# design.net
KiCad netlist of a schematic drawn in Altium Designer
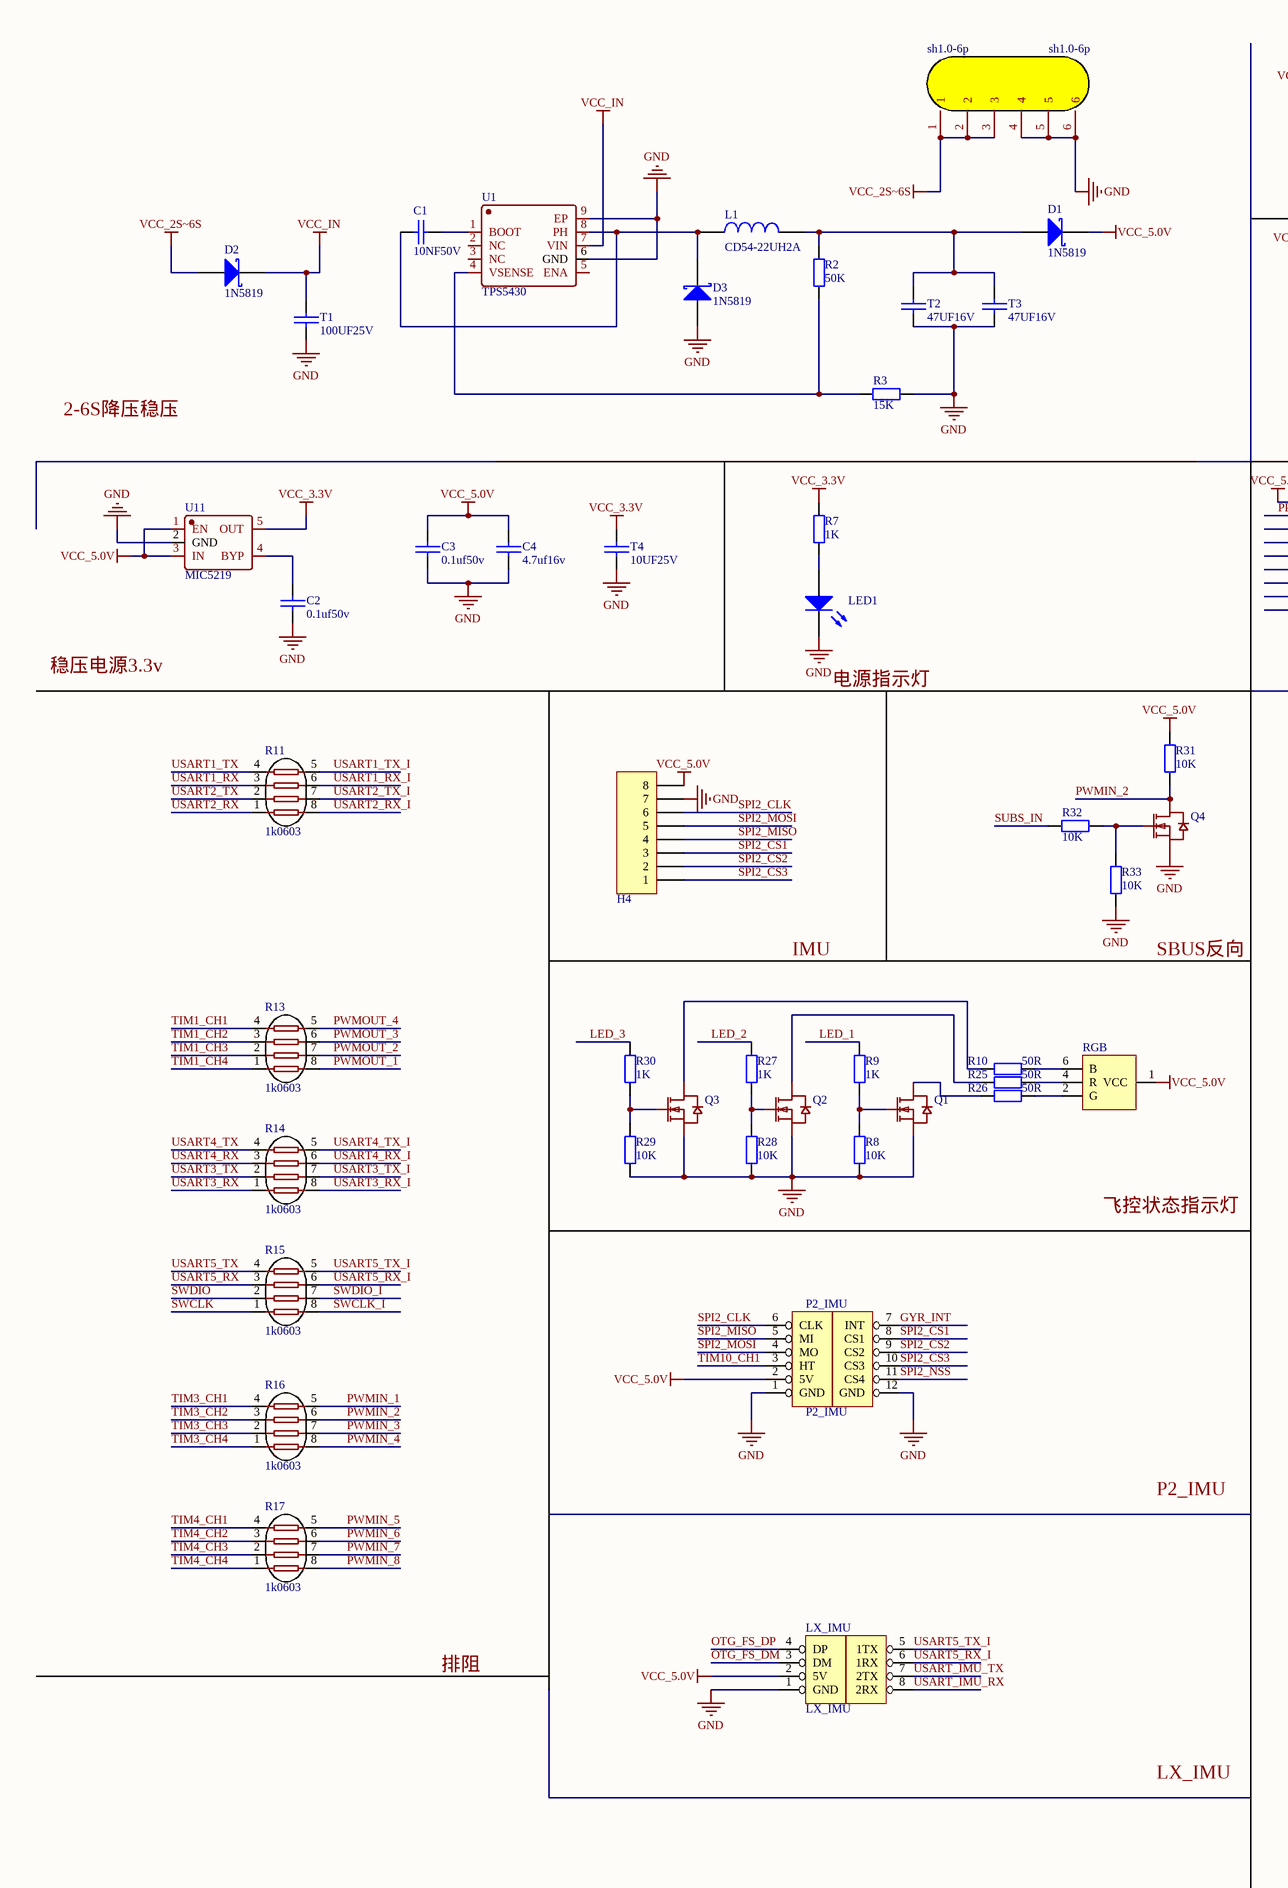
[diagram p0: 飞控板.SchDoc, left]
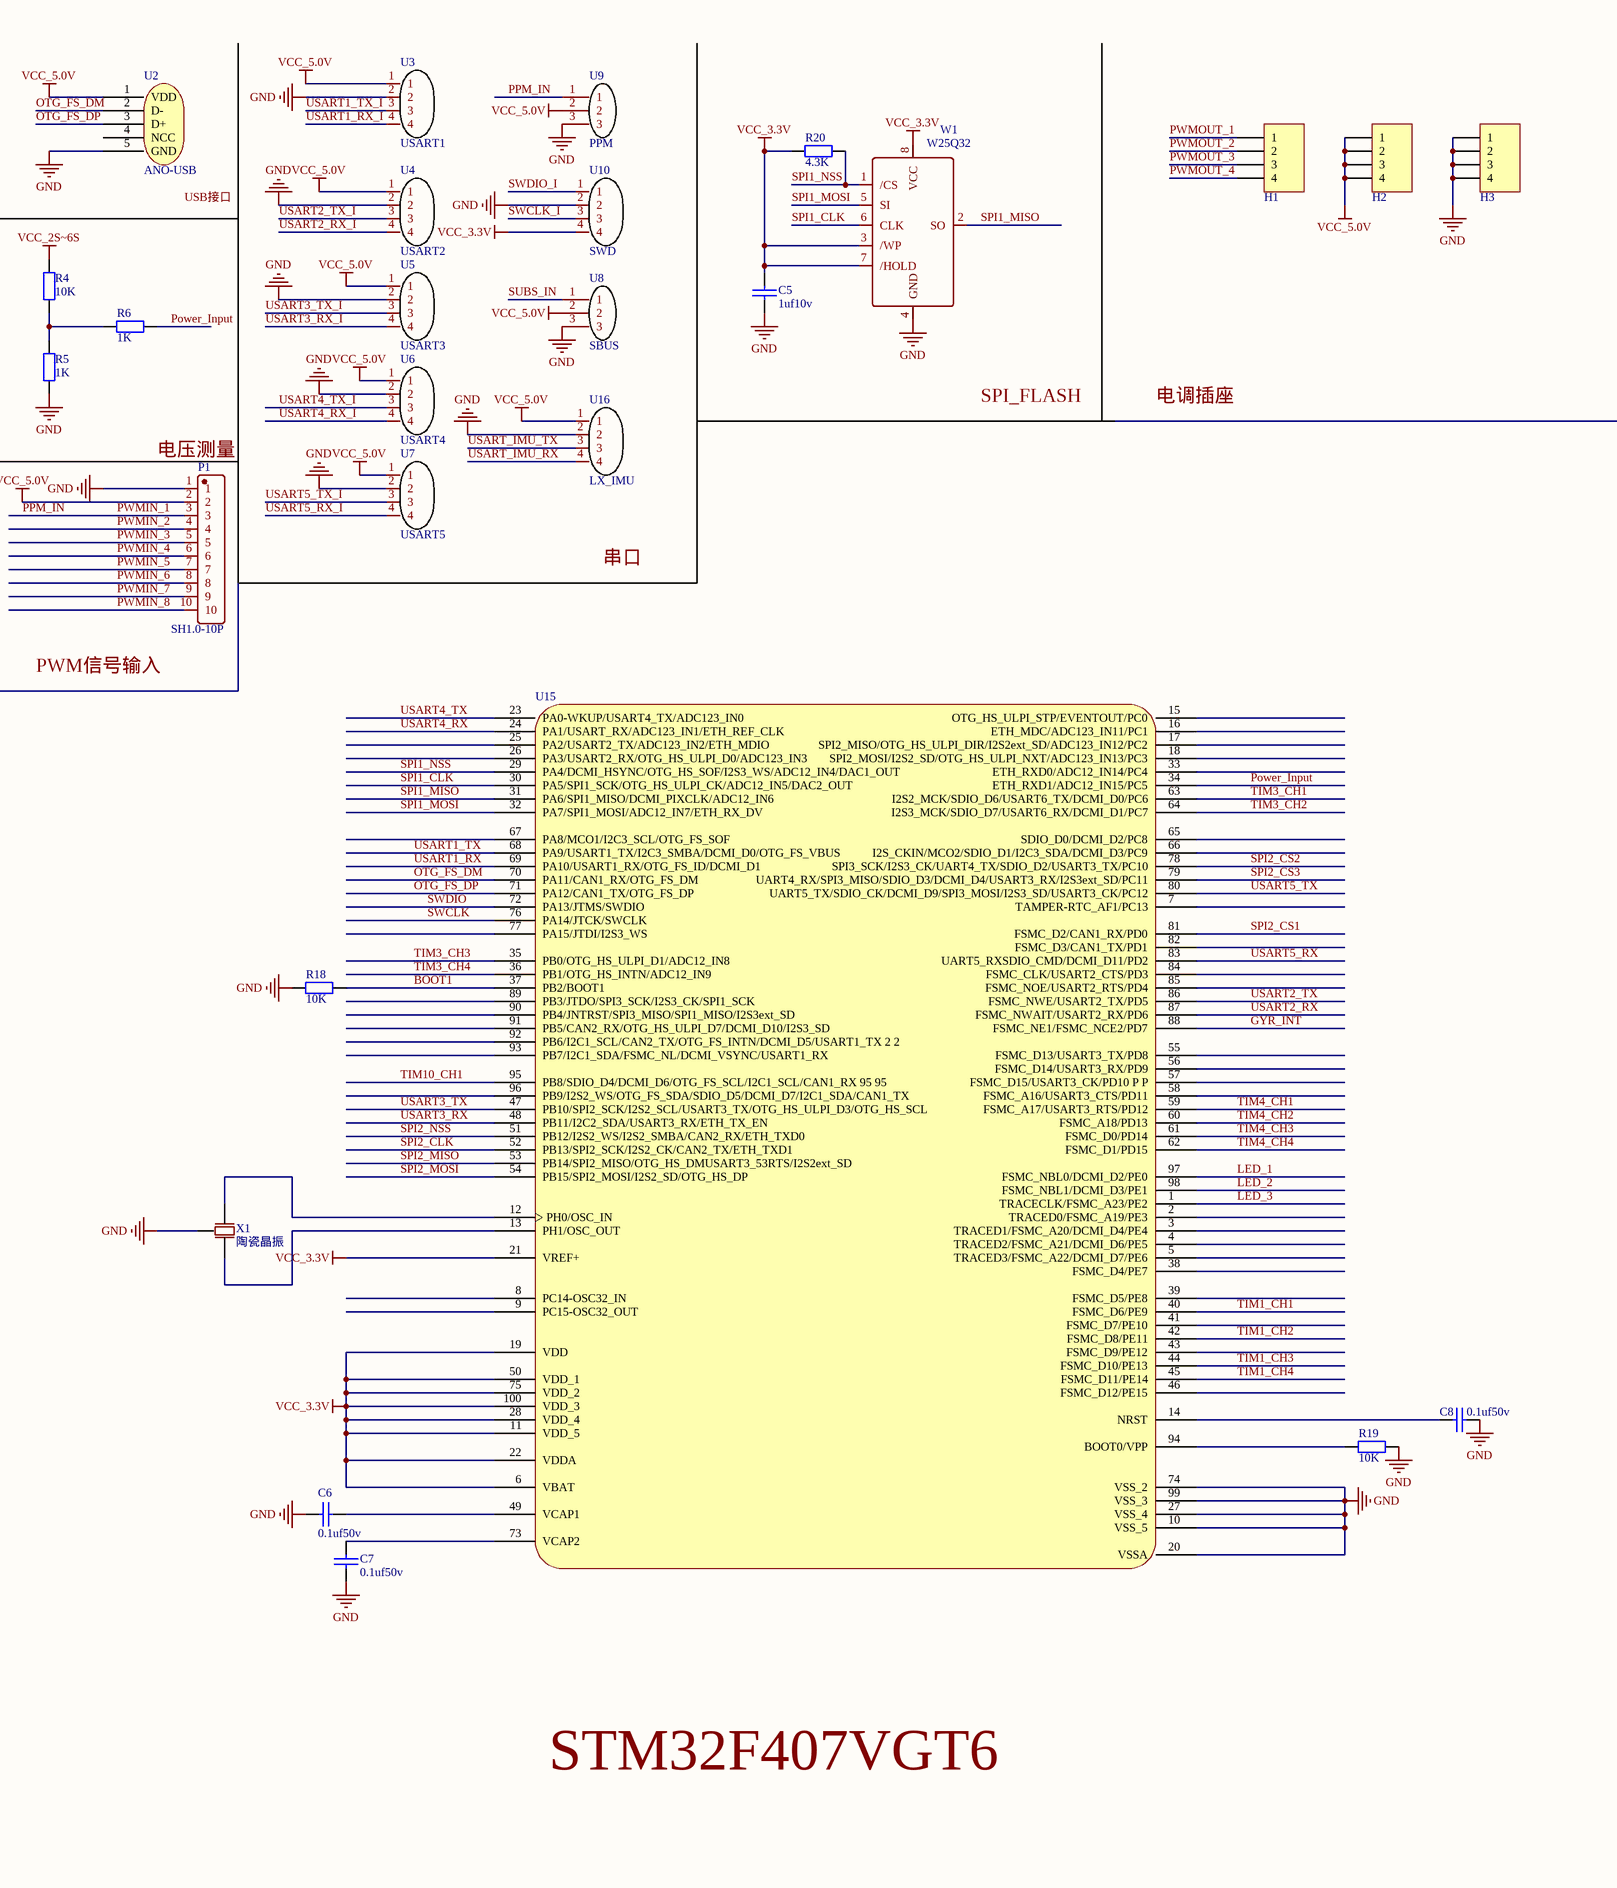
[diagram p1: 飞控板.SchDoc, right]

(export (version "E")
  (design (tool "Eeschema 10.0.6"))
  (components
    (comp (ref "C1")
      (value "10NF50V")
      (footprint "0805C")
      (description "无极性电容")
      (libsource (lib "电容") (part "CAP"))
    )
    (comp (ref "C2")
      (value "0.1uf50v")
      (footprint "0805C")
      (description "无极性电容")
      (libsource (lib "电容") (part "CAP"))
    )
    (comp (ref "C3")
      (value "0.1uf50v")
      (footprint "0805C")
      (description "无极性电容")
      (libsource (lib "电容") (part "CAP"))
    )
    (comp (ref "C4")
      (value "4.7uf16v")
      (footprint "0805C")
      (description "无极性电容")
      (libsource (lib "电容") (part "CAP"))
    )
    (comp (ref "C5")
      (value "1uf10v")
      (footprint "0805C")
      (description "无极性电容")
      (libsource (lib "电容") (part "CAP"))
    )
    (comp (ref "C6")
      (value "0.1uf50v")
      (footprint "0805C")
      (description "无极性电容")
      (libsource (lib "电容") (part "CAP"))
    )
    (comp (ref "C7")
      (value "0.1uf50v")
      (footprint "0805C")
      (description "无极性电容")
      (libsource (lib "电容") (part "CAP"))
    )
    (comp (ref "C8")
      (value "0.1uf50v")
      (footprint "0805C")
      (description "无极性电容")
      (libsource (lib "电容") (part "CAP"))
    )
    (comp (ref "D1")
      (value "1N5819")
      (footprint "DO214AC_SMA")
      (description "贴片肖特基二极管")
      (libsource (lib "1.二极管") (part "1N5817-5819SMD"))
    )
    (comp (ref "D2")
      (value "1N5819")
      (footprint "DO214AC_SMA")
      (description "贴片肖特基二极管")
      (libsource (lib "1.二极管") (part "1N5817-5819SMD"))
    )
    (comp (ref "D3")
      (value "1N5819")
      (footprint "DO214AC_SMA")
      (description "贴片肖特基二极管")
      (libsource (lib "1.二极管") (part "1N5817-5819SMD"))
    )
    (comp (ref "H1")
      (value "Header 4")
      (footprint "HDR1X4")
      (description "Header, 4-Pin")
      (fields (field (name "PUBLISHER") "Altium Limited"))
      (libsource (lib "9.接插件 连接器") (part "Header 4"))
    )
    (comp (ref "H2")
      (value "Header 4")
      (footprint "HDR1X4")
      (description "Header, 4-Pin")
      (fields (field (name "PUBLISHER") "Altium Limited"))
      (libsource (lib "9.接插件 连接器") (part "Header 4"))
    )
    (comp (ref "H3")
      (value "Header 4")
      (footprint "HDR1X4")
      (description "Header, 4-Pin")
      (fields (field (name "PUBLISHER") "Altium Limited"))
      (libsource (lib "9.接插件 连接器") (part "Header 4"))
    )
    (comp (ref "H4")
      (value "Header 8")
      (footprint "HDR1X8")
      (description "Header, 8-Pin")
      (fields (field (name "PUBLISHER") "Altium Limited"))
      (libsource (lib "9.接插件 连接器") (part "Header 8"))
    )
    (comp (ref "L1")
      (value "CD54-22UH2A")
      (footprint "CDRH73")
      (description "INDUCTOR")
      (libsource (lib "电感") (part "INDUCTOR"))
    )
    (comp (ref "LED1") (value "~") (footprint "LED-1206") (libsource (lib "1.二极管") (part "LED1206")))
    (comp (ref "LX_IMU") (value "LX_IMU") (footprint "LX_IMU") (libsource (lib "LX_IMU") (part "LX_IMU")))
    (comp (ref "P1")
      (value "SH1.0-10P")
      (footprint "SH1.0-10P")
      (libsource (lib "SH1.0-10P") (part "SH1.0-10P"))
    )
    (comp (ref "P2_IMU")
      (value "P2_IMU")
      (footprint "P2_IMU")
      (libsource (lib "P2_IMU") (part "Component_1"))
    )
    (comp (ref "Q1") (value "~") (footprint "SI2310") (libsource (lib "SI2310") (part "SI2310")))
    (comp (ref "Q2") (value "~") (footprint "SI2310") (libsource (lib "SI2310") (part "SI2310")))
    (comp (ref "Q3") (value "~") (footprint "SI2310") (libsource (lib "SI2310") (part "SI2310")))
    (comp (ref "Q4") (value "~") (footprint "SI2310") (libsource (lib "SI2310") (part "SI2310")))
    (comp (ref "R2")
      (value "50K")
      (footprint "0805R")
      (description "0805贴片电阻")
      (libsource (lib "") (part "Res_0805_2"))
    )
    (comp (ref "R3")
      (value "15K")
      (footprint "0805R")
      (description "0805贴片电阻")
      (libsource (lib "0.电阻电容电感") (part "Res_0805"))
    )
    (comp (ref "R4")
      (value "10K")
      (footprint "0805R")
      (description "0805贴片电阻")
      (libsource (lib "") (part "Res_0805_2"))
    )
    (comp (ref "R5")
      (value "1K")
      (footprint "0805R")
      (description "0805贴片电阻")
      (libsource (lib "") (part "Res_0805_2"))
    )
    (comp (ref "R6")
      (value "1K")
      (footprint "0805R")
      (description "0805贴片电阻")
      (libsource (lib "0.电阻电容电感") (part "Res_0805"))
    )
    (comp (ref "R7")
      (value "1K")
      (footprint "0805R")
      (description "0805贴片电阻")
      (libsource (lib "") (part "Res_0805_2"))
    )
    (comp (ref "R8")
      (value "10K")
      (footprint "0805R")
      (description "0805贴片电阻")
      (libsource (lib "") (part "Res_0805_2"))
    )
    (comp (ref "R9")
      (value "1K")
      (footprint "0805R")
      (description "0805贴片电阻")
      (libsource (lib "") (part "Res_0805_2"))
    )
    (comp (ref "R10")
      (value "50R")
      (footprint "0805R")
      (description "0805贴片电阻")
      (libsource (lib "") (part "Res_0805_1"))
    )
    (comp (ref "R11") (value "1k0603") (footprint "1k0603") (libsource (lib "1k0603") (part "1k0603")))
    (comp (ref "R13") (value "1k0603") (footprint "1k0603") (libsource (lib "1k0603") (part "1k0603")))
    (comp (ref "R14") (value "1k0603") (footprint "1k0603") (libsource (lib "1k0603") (part "1k0603")))
    (comp (ref "R15") (value "1k0603") (footprint "1k0603") (libsource (lib "1k0603") (part "1k0603")))
    (comp (ref "R16") (value "1k0603") (footprint "1k0603") (libsource (lib "1k0603") (part "1k0603")))
    (comp (ref "R17") (value "1k0603") (footprint "1k0603") (libsource (lib "1k0603") (part "1k0603")))
    (comp (ref "R18")
      (value "10K")
      (footprint "0805R")
      (description "0805贴片电阻")
      (libsource (lib "") (part "Res_0805_1"))
    )
    (comp (ref "R19")
      (value "10K")
      (footprint "0805R")
      (description "0805贴片电阻")
      (libsource (lib "") (part "Res_0805_1"))
    )
    (comp (ref "R20")
      (value "4.3K")
      (footprint "0805R")
      (description "0805贴片电阻")
      (libsource (lib "") (part "Res_0805_1"))
    )
    (comp (ref "R25")
      (value "50R")
      (footprint "0805R")
      (description "0805贴片电阻")
      (libsource (lib "") (part "Res_0805_1"))
    )
    (comp (ref "R26")
      (value "50R")
      (footprint "0805R")
      (description "0805贴片电阻")
      (libsource (lib "") (part "Res_0805_1"))
    )
    (comp (ref "R27")
      (value "1K")
      (footprint "0805R")
      (description "0805贴片电阻")
      (libsource (lib "") (part "Res_0805_2"))
    )
    (comp (ref "R28")
      (value "10K")
      (footprint "0805R")
      (description "0805贴片电阻")
      (libsource (lib "") (part "Res_0805_2"))
    )
    (comp (ref "R29")
      (value "10K")
      (footprint "0805R")
      (description "0805贴片电阻")
      (libsource (lib "") (part "Res_0805_2"))
    )
    (comp (ref "R30")
      (value "1K")
      (footprint "0805R")
      (description "0805贴片电阻")
      (libsource (lib "") (part "Res_0805_2"))
    )
    (comp (ref "R31")
      (value "10K")
      (footprint "0805R")
      (description "0805贴片电阻")
      (libsource (lib "") (part "Res_0805_2"))
    )
    (comp (ref "R32")
      (value "10K")
      (footprint "0805R")
      (description "0805贴片电阻")
      (libsource (lib "0.电阻电容电感") (part "Res_0805"))
    )
    (comp (ref "R33")
      (value "10K")
      (footprint "0805R")
      (description "0805贴片电阻")
      (libsource (lib "") (part "Res_0805_3"))
    )
    (comp (ref "RGB")
      (value "~")
      (footprint "RGB_LED")
      (description "RGB")
      (libsource (lib "RGB灯") (part "RGB"))
    )
    (comp (ref "sh1.0-6p")
      (value "sh1.0-6p")
      (footprint "sh1.0-6p")
      (libsource (lib "sh1.0-6p") (part "sh1.0-6p"))
    )
    (comp (ref "T1")
      (value "100UF25V")
      (footprint "0805C")
      (description "无极性电容")
      (libsource (lib "电容") (part "CAP"))
    )
    (comp (ref "T2")
      (value "47UF16V")
      (footprint "0805C")
      (description "无极性电容")
      (libsource (lib "电容") (part "CAP"))
    )
    (comp (ref "T3")
      (value "47UF16V")
      (footprint "0805C")
      (description "无极性电容")
      (libsource (lib "电容") (part "CAP"))
    )
    (comp (ref "T4")
      (value "10UF25V")
      (footprint "0805C")
      (description "无极性电容")
      (libsource (lib "电容") (part "CAP"))
    )
    (comp (ref "U1") (value "TPS5430") (footprint "TPS5430") (libsource (lib "TPS5430") (part "TPS5430")))
    (comp (ref "U2") (value "ANO-USB") (footprint "ANO-USB") (libsource (lib "ANO-USB") (part "ANO-USB")))
    (comp (ref "U3") (value "USART1") (footprint "SH1.0-4P") (libsource (lib "SH1.0-4P") (part "SH1.0-4P")))
    (comp (ref "U4") (value "USART2") (footprint "SH1.0-4P") (libsource (lib "SH1.0-4P") (part "SH1.0-4P")))
    (comp (ref "U5") (value "USART3") (footprint "SH1.0-4P") (libsource (lib "SH1.0-4P") (part "SH1.0-4P")))
    (comp (ref "U6") (value "USART4") (footprint "SH1.0-4P") (libsource (lib "SH1.0-4P") (part "SH1.0-4P")))
    (comp (ref "U7") (value "USART5") (footprint "SH1.0-4P") (libsource (lib "SH1.0-4P") (part "SH1.0-4P")))
    (comp (ref "U8") (value "SBUS") (footprint "SH1.0-3P") (libsource (lib "SH1.0-3P") (part "SH1.0-3P")))
    (comp (ref "U9") (value "PPM") (footprint "SH1.0-3P") (libsource (lib "SH1.0-3P") (part "SH1.0-3P")))
    (comp (ref "U10") (value "SWD") (footprint "SH1.0-4P") (libsource (lib "SH1.0-4P") (part "SH1.0-4P")))
    (comp (ref "U11") (value "MIC5219") (footprint "MIC5219") (libsource (lib "MIC5219") (part "MIC5219")))
    (comp (ref "U15")
      (value "~")
      (footprint "STM32F407VGT6=")
      (libsource (lib "STM32F407VGT6=") (part "STM32F407VGT6="))
    )
    (comp (ref "U16") (value "LX_IMU") (footprint "SH1.0-4P") (libsource (lib "SH1.0-4P") (part "SH1.0-4P")))
    (comp (ref "W1") (value "W25Q32") (footprint "W25Q32") (libsource (lib "W25Q32") (part "W25Q32")))
    (comp (ref "X1") (value "陶瓷晶振") (footprint "陶瓷晶振") (libsource (lib "陶瓷晶振") (part "陶瓷晶振")))
  )
  (nets
    (net (code "2") (name "/BOOT1") (class "Default")
      (node (ref "R18") (pin "1") (pinfunction "1_1") (pintype "passive"))
      (node (ref "U15") (pin "37") (pinfunction "PB2/BOOT1_37") (pintype "passive"))
    )
    (net (code "3") (name "/GYR_INT") (class "Default")
      (node (ref "P2_IMU") (pin "7") (pinfunction "INT_7") (pintype "passive"))
      (node (ref "U15") (pin "88") (pinfunction "FSMC_NE1/FSMC_NCE2/PD7_88") (pintype "passive"))
    )
    (net (code "5") (name "/LED_1") (class "Default")
      (node (ref "R9") (pin "1") (pinfunction "1_1") (pintype "passive"))
      (node (ref "U15") (pin "97") (pinfunction "FSMC_NBL0/DCMI_D2/PE0_97") (pintype "passive"))
    )
    (net (code "6") (name "/LED_2") (class "Default")
      (node (ref "R27") (pin "1") (pinfunction "1_1") (pintype "passive"))
      (node (ref "U15") (pin "98") (pinfunction "FSMC_NBL1/DCMI_D3/PE1_98") (pintype "passive"))
    )
    (net (code "7") (name "/LED_3") (class "Default")
      (node (ref "R30") (pin "1") (pinfunction "1_1") (pintype "passive"))
      (node (ref "U15") (pin "1") (pinfunction "TRACECLK/FSMC_A23/PE2_1") (pintype "passive"))
    )
    (net (code "9") (name "/OTG_FS_DM") (class "Default")
      (node (ref "LX_IMU") (pin "3") (pinfunction "DM_3") (pintype "passive"))
      (node (ref "U15") (pin "70") (pinfunction "PA11/CAN1_RX/OTG_FS_DM_70") (pintype "passive"))
      (node (ref "U2") (pin "2") (pinfunction "D-_2") (pintype "passive"))
    )
    (net (code "10") (name "/OTG_FS_DP") (class "Default")
      (node (ref "LX_IMU") (pin "4") (pinfunction "DP_4") (pintype "passive"))
      (node (ref "U15") (pin "71") (pinfunction "PA12/CAN1_TX/OTG_FS_DP_71") (pintype "passive"))
      (node (ref "U2") (pin "3") (pinfunction "D+_3") (pintype "passive"))
    )
    (net (code "12") (name "/PPM_IN") (class "Default")
      (node (ref "P1") (pin "3") (pinfunction "3_3") (pintype "passive"))
      (node (ref "R16") (pin "5") (pinfunction "5_5") (pintype "passive"))
      (node (ref "U9") (pin "1") (pinfunction "1_1") (pintype "passive"))
    )
    (net (code "13") (name "/PWMIN_2") (class "Default")
      (node (ref "P1") (pin "4") (pinfunction "4_4") (pintype "passive"))
      (node (ref "Q4") (pin "3") (pinfunction "D_3") (pintype "passive"))
      (node (ref "R16") (pin "6") (pinfunction "6_6") (pintype "passive"))
      (node (ref "R31") (pin "2") (pinfunction "2_2") (pintype "passive"))
    )
    (net (code "14") (name "/PWMIN_3") (class "Default")
      (node (ref "P1") (pin "5") (pinfunction "5_5") (pintype "passive"))
      (node (ref "R16") (pin "7") (pinfunction "7_7") (pintype "passive"))
    )
    (net (code "15") (name "/PWMIN_4") (class "Default")
      (node (ref "P1") (pin "6") (pinfunction "6_6") (pintype "passive"))
      (node (ref "R16") (pin "8") (pinfunction "8_8") (pintype "passive"))
    )
    (net (code "16") (name "/PWMIN_5") (class "Default")
      (node (ref "P1") (pin "7") (pinfunction "7_7") (pintype "passive"))
      (node (ref "R17") (pin "5") (pinfunction "5_5") (pintype "passive"))
    )
    (net (code "17") (name "/PWMIN_6") (class "Default")
      (node (ref "P1") (pin "8") (pinfunction "8_8") (pintype "passive"))
      (node (ref "R17") (pin "6") (pinfunction "6_6") (pintype "passive"))
    )
    (net (code "18") (name "/PWMIN_7") (class "Default")
      (node (ref "P1") (pin "9") (pinfunction "9_9") (pintype "passive"))
      (node (ref "R17") (pin "7") (pinfunction "7_7") (pintype "passive"))
    )
    (net (code "19") (name "/PWMIN_8") (class "Default")
      (node (ref "P1") (pin "10") (pinfunction "10_10") (pintype "passive"))
      (node (ref "R17") (pin "8") (pinfunction "8_8") (pintype "passive"))
    )
    (net (code "20") (name "/PWMOUT_1") (class "Default")
      (node (ref "H1") (pin "1") (pinfunction "1_1") (pintype "passive"))
      (node (ref "R13") (pin "8") (pinfunction "8_8") (pintype "passive"))
    )
    (net (code "21") (name "/PWMOUT_2") (class "Default")
      (node (ref "H1") (pin "2") (pinfunction "2_2") (pintype "passive"))
      (node (ref "R13") (pin "7") (pinfunction "7_7") (pintype "passive"))
    )
    (net (code "22") (name "/PWMOUT_3") (class "Default")
      (node (ref "H1") (pin "3") (pinfunction "3_3") (pintype "passive"))
      (node (ref "R13") (pin "6") (pinfunction "6_6") (pintype "passive"))
    )
    (net (code "23") (name "/PWMOUT_4") (class "Default")
      (node (ref "H1") (pin "4") (pinfunction "4_4") (pintype "passive"))
      (node (ref "R13") (pin "5") (pinfunction "5_5") (pintype "passive"))
    )
    (net (code "25") (name "/Power_Input") (class "Default")
      (node (ref "R6") (pin "2") (pinfunction "2_2") (pintype "passive"))
      (node (ref "U15") (pin "34") (pinfunction "ETH_RXD1/ADC12_IN15/PC5_34") (pintype "passive"))
    )
    (net (code "27") (name "/SPI1_CLK") (class "Default")
      (node (ref "U15") (pin "30") (pinfunction "PA5/SPI1_SCK/OTG_HS_ULPI_CK/ADC12_IN5/DAC2_OUT_30") (pintype "passive"))
      (node (ref "W1") (pin "6") (pinfunction "CLK_6") (pintype "passive"))
    )
    (net (code "28") (name "/SPI1_MISO") (class "Default")
      (node (ref "U15") (pin "31") (pinfunction "PA6/SPI1_MISO/DCMI_PIXCLK/ADC12_IN6_31") (pintype "passive"))
      (node (ref "W1") (pin "2") (pinfunction "SO_2") (pintype "passive"))
    )
    (net (code "29") (name "/SPI1_MOSI") (class "Default")
      (node (ref "U15") (pin "32") (pinfunction "PA7/SPI1_MOSI/ADC12_IN7/ETH_RX_DV_32") (pintype "passive"))
      (node (ref "W1") (pin "5") (pinfunction "SI_5") (pintype "passive"))
    )
    (net (code "30") (name "/SPI1_NSS") (class "Default")
      (node (ref "R20") (pin "1") (pinfunction "1_1") (pintype "passive"))
      (node (ref "U15") (pin "29") (pinfunction "PA4/DCMI_HSYNC/OTG_HS_SOF/I2S3_WS/ADC12_IN4/DAC1_OUT_29") (pintype "passive"))
      (node (ref "W1") (pin "1") (pinfunction "/CS_1") (pintype "passive"))
    )
    (net (code "31") (name "/SPI2_CLK") (class "Default")
      (node (ref "H4") (pin "6") (pinfunction "6_6") (pintype "passive"))
      (node (ref "P2_IMU") (pin "6") (pinfunction "CLK_6") (pintype "passive"))
      (node (ref "U15") (pin "52") (pinfunction "PB13/SPI2_SCK/I2S2_CK/CAN2_TX/ETH_TXD1_52") (pintype "passive"))
    )
    (net (code "32") (name "/SPI2_CS1") (class "Default")
      (node (ref "H4") (pin "3") (pinfunction "3_3") (pintype "passive"))
      (node (ref "P2_IMU") (pin "8") (pinfunction "CS1_8") (pintype "passive"))
      (node (ref "U15") (pin "81") (pinfunction "FSMC_D2/CAN1_RX/PD0_81") (pintype "passive"))
    )
    (net (code "33") (name "/SPI2_CS2") (class "Default")
      (node (ref "H4") (pin "2") (pinfunction "2_2") (pintype "passive"))
      (node (ref "P2_IMU") (pin "9") (pinfunction "CS2_9") (pintype "passive"))
      (node (ref "U15") (pin "78") (pinfunction "SPI3_SCK/I2S3_CK/UART4_TX/SDIO_D2/USART3_TX/PC10_78") (pintype "passive"))
    )
    (net (code "34") (name "/SPI2_CS3") (class "Default")
      (node (ref "H4") (pin "1") (pinfunction "1_1") (pintype "passive"))
      (node (ref "P2_IMU") (pin "10") (pinfunction "CS3_10") (pintype "passive"))
      (node (ref "U15") (pin "79") (pinfunction "UART4_RX/SPI3_MISO/SDIO_D3/DCMI_D4/USART3_RX/I2S3ext_SD/PC11_79") (pintype "passive"))
    )
    (net (code "35") (name "/SPI2_MISO") (class "Default")
      (node (ref "H4") (pin "4") (pinfunction "4_4") (pintype "passive"))
      (node (ref "P2_IMU") (pin "5") (pinfunction "MI_5") (pintype "passive"))
      (node (ref "U15") (pin "53") (pinfunction "PB14/SPI2_MISO/OTG_HS_DMUSART3_53RTS/I2S2ext_SD_53") (pintype "passive"))
    )
    (net (code "36") (name "/SPI2_MOSI") (class "Default")
      (node (ref "H4") (pin "5") (pinfunction "5_5") (pintype "passive"))
      (node (ref "P2_IMU") (pin "4") (pinfunction "MO_4") (pintype "passive"))
      (node (ref "U15") (pin "54") (pinfunction "PB15/SPI2_MOSI/I2S2_SD/OTG_HS_DP_54") (pintype "passive"))
    )
    (net (code "37") (name "/SPI2_NSS") (class "Default")
      (node (ref "P2_IMU") (pin "11") (pinfunction "CS4_11") (pintype "passive"))
      (node (ref "U15") (pin "51") (pinfunction "PB12/I2S2_WS/I2S2_SMBA/CAN2_RX/ETH_TXD0_51") (pintype "passive"))
    )
    (net (code "40") (name "/SUBS_IN") (class "Default")
      (node (ref "R32") (pin "1") (pinfunction "1_1") (pintype "passive"))
      (node (ref "U8") (pin "1") (pinfunction "1_1") (pintype "passive"))
    )
    (net (code "41") (name "/SWCLK") (class "Default")
      (node (ref "R15") (pin "1") (pinfunction "1_1") (pintype "passive"))
      (node (ref "U15") (pin "76") (pinfunction "PA14/JTCK/SWCLK_76") (pintype "passive"))
    )
    (net (code "42") (name "/SWCLK_I") (class "Default")
      (node (ref "R15") (pin "8") (pinfunction "8_8") (pintype "passive"))
      (node (ref "U10") (pin "3") (pinfunction "3_3") (pintype "passive"))
    )
    (net (code "43") (name "/SWDIO") (class "Default")
      (node (ref "R15") (pin "2") (pinfunction "2_2") (pintype "passive"))
      (node (ref "U15") (pin "72") (pinfunction "PA13/JTMS/SWDIO_72") (pintype "passive"))
    )
    (net (code "44") (name "/SWDIO_I") (class "Default")
      (node (ref "R15") (pin "7") (pinfunction "7_7") (pintype "passive"))
      (node (ref "U10") (pin "1") (pinfunction "1_1") (pintype "passive"))
    )
    (net (code "45") (name "/TIM1_CH1") (class "Default")
      (node (ref "R13") (pin "4") (pinfunction "4_4") (pintype "passive"))
      (node (ref "U15") (pin "40") (pinfunction "FSMC_D6/PE9_40") (pintype "passive"))
    )
    (net (code "46") (name "/TIM1_CH2") (class "Default")
      (node (ref "R13") (pin "3") (pinfunction "3_3") (pintype "passive"))
      (node (ref "U15") (pin "42") (pinfunction "FSMC_D8/PE11_42") (pintype "passive"))
    )
    (net (code "47") (name "/TIM1_CH3") (class "Default")
      (node (ref "R13") (pin "2") (pinfunction "2_2") (pintype "passive"))
      (node (ref "U15") (pin "44") (pinfunction "FSMC_D10/PE13_44") (pintype "passive"))
    )
    (net (code "48") (name "/TIM1_CH4") (class "Default")
      (node (ref "R13") (pin "1") (pinfunction "1_1") (pintype "passive"))
      (node (ref "U15") (pin "45") (pinfunction "FSMC_D11/PE14_45") (pintype "passive"))
    )
    (net (code "49") (name "/TIM3_CH1") (class "Default")
      (node (ref "R16") (pin "4") (pinfunction "4_4") (pintype "passive"))
      (node (ref "U15") (pin "63") (pinfunction "I2S2_MCK/SDIO_D6/USART6_TX/DCMI_D0/PC6_63") (pintype "passive"))
    )
    (net (code "50") (name "/TIM3_CH2") (class "Default")
      (node (ref "R16") (pin "3") (pinfunction "3_3") (pintype "passive"))
      (node (ref "U15") (pin "64") (pinfunction "I2S3_MCK/SDIO_D7/USART6_RX/DCMI_D1/PC7_64") (pintype "passive"))
    )
    (net (code "51") (name "/TIM3_CH3") (class "Default")
      (node (ref "R16") (pin "2") (pinfunction "2_2") (pintype "passive"))
      (node (ref "U15") (pin "35") (pinfunction "PB0/OTG_HS_ULPI_D1/ADC12_IN8_35") (pintype "passive"))
    )
    (net (code "52") (name "/TIM3_CH4") (class "Default")
      (node (ref "R16") (pin "1") (pinfunction "1_1") (pintype "passive"))
      (node (ref "U15") (pin "36") (pinfunction "PB1/OTG_HS_INTN/ADC12_IN9_36") (pintype "passive"))
    )
    (net (code "53") (name "/TIM4_CH1") (class "Default")
      (node (ref "R17") (pin "4") (pinfunction "4_4") (pintype "passive"))
      (node (ref "U15") (pin "59") (pinfunction "FSMC_A17/USART3_RTS/PD12_59") (pintype "passive"))
    )
    (net (code "54") (name "/TIM4_CH2") (class "Default")
      (node (ref "R17") (pin "3") (pinfunction "3_3") (pintype "passive"))
      (node (ref "U15") (pin "60") (pinfunction "FSMC_A18/PD13_60") (pintype "passive"))
    )
    (net (code "55") (name "/TIM4_CH3") (class "Default")
      (node (ref "R17") (pin "2") (pinfunction "2_2") (pintype "passive"))
      (node (ref "U15") (pin "61") (pinfunction "FSMC_D0/PD14_61") (pintype "passive"))
    )
    (net (code "56") (name "/TIM4_CH4") (class "Default")
      (node (ref "R17") (pin "1") (pinfunction "1_1") (pintype "passive"))
      (node (ref "U15") (pin "62") (pinfunction "FSMC_D1/PD15_62") (pintype "passive"))
    )
    (net (code "57") (name "/TIM10_CH1") (class "Default")
      (node (ref "P2_IMU") (pin "3") (pinfunction "HT_3") (pintype "passive"))
      (node (ref "U15") (pin "95") (pinfunction "PB8/SDIO_D4/DCMI_D6/OTG_FS_SCL/I2C1_SCL/CAN1_RX_95_95_95") (pintype "passive"))
    )
    (net (code "58") (name "/USART1_RX") (class "Default")
      (node (ref "R11") (pin "3") (pinfunction "3_3") (pintype "passive"))
      (node (ref "U15") (pin "69") (pinfunction "PA10/USART1_RX/OTG_FS_ID/DCMI_D1_69") (pintype "passive"))
    )
    (net (code "59") (name "/USART1_RX_I") (class "Default")
      (node (ref "R11") (pin "6") (pinfunction "6_6") (pintype "passive"))
      (node (ref "U3") (pin "4") (pinfunction "4_4") (pintype "passive"))
    )
    (net (code "60") (name "/USART1_TX") (class "Default")
      (node (ref "R11") (pin "4") (pinfunction "4_4") (pintype "passive"))
      (node (ref "U15") (pin "68") (pinfunction "PA9/USART1_TX/I2C3_SMBA/DCMI_D0/OTG_FS_VBUS_68") (pintype "passive"))
    )
    (net (code "61") (name "/USART1_TX_I") (class "Default")
      (node (ref "R11") (pin "5") (pinfunction "5_5") (pintype "passive"))
      (node (ref "U3") (pin "3") (pinfunction "3_3") (pintype "passive"))
    )
    (net (code "62") (name "/USART2_RX") (class "Default")
      (node (ref "R11") (pin "1") (pinfunction "1_1") (pintype "passive"))
      (node (ref "U15") (pin "87") (pinfunction "FSMC_NWAIT/USART2_RX/PD6_87") (pintype "passive"))
    )
    (net (code "63") (name "/USART2_RX_I") (class "Default")
      (node (ref "R11") (pin "8") (pinfunction "8_8") (pintype "passive"))
      (node (ref "U4") (pin "4") (pinfunction "4_4") (pintype "passive"))
    )
    (net (code "64") (name "/USART2_TX") (class "Default")
      (node (ref "R11") (pin "2") (pinfunction "2_2") (pintype "passive"))
      (node (ref "U15") (pin "86") (pinfunction "FSMC_NWE/USART2_TX/PD5_86") (pintype "passive"))
    )
    (net (code "65") (name "/USART2_TX_I") (class "Default")
      (node (ref "R11") (pin "7") (pinfunction "7_7") (pintype "passive"))
      (node (ref "U4") (pin "3") (pinfunction "3_3") (pintype "passive"))
    )
    (net (code "66") (name "/USART3_RX") (class "Default")
      (node (ref "R14") (pin "1") (pinfunction "1_1") (pintype "passive"))
      (node (ref "U15") (pin "48") (pinfunction "PB11/I2C2_SDA/USART3_RX/ETH_TX_EN_48") (pintype "passive"))
    )
    (net (code "67") (name "/USART3_RX_I") (class "Default")
      (node (ref "R14") (pin "8") (pinfunction "8_8") (pintype "passive"))
      (node (ref "U5") (pin "4") (pinfunction "4_4") (pintype "passive"))
    )
    (net (code "68") (name "/USART3_TX") (class "Default")
      (node (ref "R14") (pin "2") (pinfunction "2_2") (pintype "passive"))
      (node (ref "U15") (pin "47") (pinfunction "PB10/SPI2_SCK/I2S2_SCL/USART3_TX/OTG_HS_ULPI_D3/OTG_HS_SCL_47") (pintype "passive"))
    )
    (net (code "69") (name "/USART3_TX_I") (class "Default")
      (node (ref "R14") (pin "7") (pinfunction "7_7") (pintype "passive"))
      (node (ref "U5") (pin "3") (pinfunction "3_3") (pintype "passive"))
    )
    (net (code "70") (name "/USART4_RX") (class "Default")
      (node (ref "R14") (pin "3") (pinfunction "3_3") (pintype "passive"))
      (node (ref "U15") (pin "24") (pinfunction "PA1/USART_RX/ADC123_IN1/ETH_REF_CLK_24") (pintype "passive"))
    )
    (net (code "71") (name "/USART4_RX_I") (class "Default")
      (node (ref "R14") (pin "6") (pinfunction "6_6") (pintype "passive"))
      (node (ref "U6") (pin "4") (pinfunction "4_4") (pintype "passive"))
    )
    (net (code "72") (name "/USART4_TX") (class "Default")
      (node (ref "R14") (pin "4") (pinfunction "4_4") (pintype "passive"))
      (node (ref "U15") (pin "23") (pinfunction "PA0-WKUP/USART4_TX/ADC123_IN0_23") (pintype "passive"))
    )
    (net (code "73") (name "/USART4_TX_I") (class "Default")
      (node (ref "R14") (pin "5") (pinfunction "5_5") (pintype "passive"))
      (node (ref "U6") (pin "3") (pinfunction "3_3") (pintype "passive"))
    )
    (net (code "74") (name "/USART5_RX") (class "Default")
      (node (ref "R15") (pin "3") (pinfunction "3_3") (pintype "passive"))
      (node (ref "U15") (pin "83") (pinfunction "UART5_RXSDIO_CMD/DCMI_D11/PD2_83") (pintype "passive"))
    )
    (net (code "75") (name "/USART5_RX_I") (class "Default")
      (node (ref "LX_IMU") (pin "6") (pinfunction "1RX_6") (pintype "passive"))
      (node (ref "R15") (pin "6") (pinfunction "6_6") (pintype "passive"))
      (node (ref "U7") (pin "4") (pinfunction "4_4") (pintype "passive"))
    )
    (net (code "76") (name "/USART5_TX") (class "Default")
      (node (ref "R15") (pin "4") (pinfunction "4_4") (pintype "passive"))
      (node (ref "U15") (pin "80") (pinfunction "UART5_TX/SDIO_CK/DCMI_D9/SPI3_MOSI/I2S3_SD/USART3_CK/PC12_80") (pintype "passive"))
    )
    (net (code "77") (name "/USART5_TX_I") (class "Default")
      (node (ref "LX_IMU") (pin "5") (pinfunction "1TX_5") (pintype "passive"))
      (node (ref "R15") (pin "5") (pinfunction "5_5") (pintype "passive"))
      (node (ref "U7") (pin "3") (pinfunction "3_3") (pintype "passive"))
    )
    (net (code "78") (name "/USART_IMU_RX") (class "Default")
      (node (ref "LX_IMU") (pin "8") (pinfunction "2RX_8") (pintype "passive"))
      (node (ref "U16") (pin "4") (pinfunction "4_4") (pintype "passive"))
    )
    (net (code "79") (name "/USART_IMU_TX") (class "Default")
      (node (ref "LX_IMU") (pin "7") (pinfunction "2TX_7") (pintype "passive"))
      (node (ref "U16") (pin "3") (pinfunction "3_3") (pintype "passive"))
    )
    (net (code "88") (name "GND") (class "Default")
      (node (ref "C2") (pin "1") (pinfunction "1_1") (pintype "passive"))
      (node (ref "C3") (pin "1") (pinfunction "1_1") (pintype "passive"))
      (node (ref "C4") (pin "1") (pinfunction "1_1") (pintype "passive"))
      (node (ref "C5") (pin "1") (pinfunction "1_1") (pintype "passive"))
      (node (ref "C6") (pin "1") (pinfunction "1_1") (pintype "passive"))
      (node (ref "C7") (pin "1") (pinfunction "1_1") (pintype "passive"))
      (node (ref "C8") (pin "2") (pinfunction "2_2") (pintype "passive"))
      (node (ref "D3") (pin "1") (pinfunction "A_1") (pintype "passive"))
      (node (ref "H3") (pin "1") (pinfunction "1_1") (pintype "passive"))
      (node (ref "H3") (pin "2") (pinfunction "2_2") (pintype "passive"))
      (node (ref "H3") (pin "3") (pinfunction "3_3") (pintype "passive"))
      (node (ref "H3") (pin "4") (pinfunction "4_4") (pintype "passive"))
      (node (ref "H4") (pin "7") (pinfunction "7_7") (pintype "passive"))
      (node (ref "LED1") (pin "2") (pinfunction "K_2") (pintype "passive"))
      (node (ref "LX_IMU") (pin "1") (pinfunction "GND_1") (pintype "passive"))
      (node (ref "P1") (pin "1") (pinfunction "1_1") (pintype "passive"))
      (node (ref "P2_IMU") (pin "1") (pinfunction "GND_1") (pintype "passive"))
      (node (ref "P2_IMU") (pin "12") (pinfunction "GND_12") (pintype "passive"))
      (node (ref "Q1") (pin "2") (pinfunction "S_2") (pintype "passive"))
      (node (ref "Q2") (pin "2") (pinfunction "S_2") (pintype "passive"))
      (node (ref "Q3") (pin "2") (pinfunction "S_2") (pintype "passive"))
      (node (ref "Q4") (pin "2") (pinfunction "S_2") (pintype "passive"))
      (node (ref "R18") (pin "2") (pinfunction "2_2") (pintype "passive"))
      (node (ref "R19") (pin "1") (pinfunction "1_1") (pintype "passive"))
      (node (ref "R28") (pin "2") (pinfunction "2_2") (pintype "passive"))
      (node (ref "R29") (pin "2") (pinfunction "2_2") (pintype "passive"))
      (node (ref "R3") (pin "2") (pinfunction "2_2") (pintype "passive"))
      (node (ref "R33") (pin "1") (pinfunction "1_1") (pintype "passive"))
      (node (ref "R5") (pin "2") (pinfunction "2_2") (pintype "passive"))
      (node (ref "R8") (pin "2") (pinfunction "2_2") (pintype "passive"))
      (node (ref "T1") (pin "2") (pinfunction "2_2") (pintype "passive"))
      (node (ref "T2") (pin "2") (pinfunction "2_2") (pintype "passive"))
      (node (ref "T3") (pin "2") (pinfunction "2_2") (pintype "passive"))
      (node (ref "T4") (pin "2") (pinfunction "2_2") (pintype "passive"))
      (node (ref "U1") (pin "6") (pinfunction "GND_6") (pintype "passive"))
      (node (ref "U1") (pin "9") (pinfunction "EP_9") (pintype "passive"))
      (node (ref "U10") (pin "2") (pinfunction "2_2") (pintype "passive"))
      (node (ref "U11") (pin "2") (pinfunction "GND_2") (pintype "passive"))
      (node (ref "U15") (pin "10") (pinfunction "VSS_5_10") (pintype "passive"))
      (node (ref "U15") (pin "20") (pinfunction "VSSA_20") (pintype "passive"))
      (node (ref "U15") (pin "27") (pinfunction "VSS_4_27") (pintype "passive"))
      (node (ref "U15") (pin "74") (pinfunction "VSS_2_74") (pintype "passive"))
      (node (ref "U15") (pin "99") (pinfunction "VSS_3_99") (pintype "passive"))
      (node (ref "U16") (pin "2") (pinfunction "2_2") (pintype "passive"))
      (node (ref "U2") (pin "5") (pinfunction "GND_5") (pintype "passive"))
      (node (ref "U3") (pin "2") (pinfunction "2_2") (pintype "passive"))
      (node (ref "U4") (pin "2") (pinfunction "2_2") (pintype "passive"))
      (node (ref "U5") (pin "2") (pinfunction "2_2") (pintype "passive"))
      (node (ref "U6") (pin "2") (pinfunction "2_2") (pintype "passive"))
      (node (ref "U7") (pin "2") (pinfunction "2_2") (pintype "passive"))
      (node (ref "U8") (pin "3") (pinfunction "3_3") (pintype "passive"))
      (node (ref "U9") (pin "3") (pinfunction "3_3") (pintype "passive"))
      (node (ref "W1") (pin "4") (pinfunction "GND_4") (pintype "passive"))
      (node (ref "X1") (pin "2") (pinfunction "GND_2") (pintype "passive"))
      (node (ref "sh1.0-6p") (pin "4") (pinfunction "4_4") (pintype "passive"))
      (node (ref "sh1.0-6p") (pin "5") (pinfunction "5_5") (pintype "passive"))
      (node (ref "sh1.0-6p") (pin "6") (pinfunction "6_6") (pintype "passive"))
    )
    (net (code "89") (name "Net-(D1-A)") (class "Default")
      (node (ref "D1") (pin "1") (pinfunction "A_1") (pintype "passive"))
      (node (ref "L1") (pin "2") (pinfunction "2_2") (pintype "passive"))
      (node (ref "R2") (pin "1") (pinfunction "1_1") (pintype "passive"))
      (node (ref "T2") (pin "1") (pinfunction "1_1") (pintype "passive"))
      (node (ref "T3") (pin "1") (pinfunction "1_1") (pintype "passive"))
    )
    (net (code "90") (name "Net-(D3-K)") (class "Default")
      (node (ref "C1") (pin "2") (pinfunction "2_2") (pintype "passive"))
      (node (ref "D3") (pin "2") (pinfunction "K_2") (pintype "passive"))
      (node (ref "L1") (pin "1") (pinfunction "1_1") (pintype "passive"))
      (node (ref "U1") (pin "8") (pinfunction "PH_8") (pintype "passive"))
    )
    (net (code "91") (name "Net-(LED1-A)") (class "Default")
      (node (ref "LED1") (pin "1") (pinfunction "A_1") (pintype "passive"))
      (node (ref "R7") (pin "2") (pinfunction "2_2") (pintype "passive"))
    )
    (net (code "92") (name "Net-(Q1-D)") (class "Default")
      (node (ref "Q1") (pin "3") (pinfunction "D_3") (pintype "passive"))
      (node (ref "R26") (pin "2") (pinfunction "2_2") (pintype "passive"))
    )
    (net (code "93") (name "Net-(Q1-G)") (class "Default")
      (node (ref "Q1") (pin "1") (pinfunction "G_1") (pintype "passive"))
      (node (ref "R8") (pin "1") (pinfunction "1_1") (pintype "passive"))
      (node (ref "R9") (pin "2") (pinfunction "2_2") (pintype "passive"))
    )
    (net (code "94") (name "Net-(Q2-D)") (class "Default")
      (node (ref "Q2") (pin "3") (pinfunction "D_3") (pintype "passive"))
      (node (ref "R25") (pin "2") (pinfunction "2_2") (pintype "passive"))
    )
    (net (code "95") (name "Net-(Q2-G)") (class "Default")
      (node (ref "Q2") (pin "1") (pinfunction "G_1") (pintype "passive"))
      (node (ref "R27") (pin "2") (pinfunction "2_2") (pintype "passive"))
      (node (ref "R28") (pin "1") (pinfunction "1_1") (pintype "passive"))
    )
    (net (code "96") (name "Net-(Q3-D)") (class "Default")
      (node (ref "Q3") (pin "3") (pinfunction "D_3") (pintype "passive"))
      (node (ref "R10") (pin "2") (pinfunction "2_2") (pintype "passive"))
    )
    (net (code "97") (name "Net-(Q3-G)") (class "Default")
      (node (ref "Q3") (pin "1") (pinfunction "G_1") (pintype "passive"))
      (node (ref "R29") (pin "1") (pinfunction "1_1") (pintype "passive"))
      (node (ref "R30") (pin "2") (pinfunction "2_2") (pintype "passive"))
    )
    (net (code "98") (name "Net-(Q4-G)") (class "Default")
      (node (ref "Q4") (pin "1") (pinfunction "G_1") (pintype "passive"))
      (node (ref "R32") (pin "2") (pinfunction "2_2") (pintype "passive"))
      (node (ref "R33") (pin "2") (pinfunction "2_2") (pintype "passive"))
    )
    (net (code "99") (name "Net-(R4-Pad2)") (class "Default")
      (node (ref "R4") (pin "2") (pinfunction "2_2") (pintype "passive"))
      (node (ref "R5") (pin "1") (pinfunction "1_1") (pintype "passive"))
      (node (ref "R6") (pin "1") (pinfunction "1_1") (pintype "passive"))
    )
    (net (code "100") (name "Net-(RGB-B)") (class "Default")
      (node (ref "R10") (pin "1") (pinfunction "1_1") (pintype "passive"))
      (node (ref "RGB") (pin "6") (pinfunction "B_6") (pintype "passive"))
    )
    (net (code "101") (name "Net-(RGB-G)") (class "Default")
      (node (ref "R26") (pin "1") (pinfunction "1_1") (pintype "passive"))
      (node (ref "RGB") (pin "2") (pinfunction "G_2") (pintype "passive"))
    )
    (net (code "102") (name "Net-(RGB-R)") (class "Default")
      (node (ref "R25") (pin "1") (pinfunction "1_1") (pintype "passive"))
      (node (ref "RGB") (pin "4") (pinfunction "R_4") (pintype "passive"))
    )
    (net (code "103") (name "Net-(U1-BOOT)") (class "Default")
      (node (ref "C1") (pin "1") (pinfunction "1_1") (pintype "passive"))
      (node (ref "U1") (pin "1") (pinfunction "BOOT_1") (pintype "passive"))
    )
    (net (code "104") (name "Net-(U1-VSENSE)") (class "Default")
      (node (ref "R2") (pin "2") (pinfunction "2_2") (pintype "passive"))
      (node (ref "R3") (pin "1") (pinfunction "1_1") (pintype "passive"))
      (node (ref "U1") (pin "4") (pinfunction "VSENSE_4") (pintype "passive"))
    )
    (net (code "105") (name "Net-(U11-BYP)") (class "Default")
      (node (ref "C2") (pin "2") (pinfunction "2_2") (pintype "passive"))
      (node (ref "U11") (pin "4") (pinfunction "BYP_4") (pintype "passive"))
    )
    (net (code "106") (name "Net-(U15-BOOT0{slash}VPP)") (class "Default")
      (node (ref "R19") (pin "2") (pinfunction "2_2") (pintype "passive"))
      (node (ref "U15") (pin "94") (pinfunction "BOOT0/VPP_94") (pintype "passive"))
    )
    (net (code "107") (name "Net-(U15-NRST)") (class "Default")
      (node (ref "C8") (pin "1") (pinfunction "1_1") (pintype "passive"))
      (node (ref "U15") (pin "14") (pinfunction "NRST_14") (pintype "passive"))
    )
    (net (code "108") (name "Net-(U15-PH0{slash}OSC_IN)") (class "Default")
      (node (ref "U15") (pin "12") (pinfunction "PH0/OSC_IN_12") (pintype "passive"))
      (node (ref "X1") (pin "3") (pinfunction "OSC2_3") (pintype "passive"))
    )
    (net (code "109") (name "Net-(U15-PH1{slash}OSC_OUT)") (class "Default")
      (node (ref "U15") (pin "13") (pinfunction "PH1/OSC_OUT_13") (pintype "passive"))
      (node (ref "X1") (pin "1") (pinfunction "OSC1_1") (pintype "passive"))
    )
    (net (code "110") (name "Net-(U15-VCAP1)") (class "Default")
      (node (ref "C6") (pin "2") (pinfunction "2_2") (pintype "passive"))
      (node (ref "U15") (pin "49") (pinfunction "VCAP1_49") (pintype "passive"))
    )
    (net (code "111") (name "Net-(U15-VCAP2)") (class "Default")
      (node (ref "C7") (pin "2") (pinfunction "2_2") (pintype "passive"))
      (node (ref "U15") (pin "73") (pinfunction "VCAP2_73") (pintype "passive"))
    )
    (net (code "112") (name "VCC_2S~6S") (class "Default")
      (node (ref "D2") (pin "1") (pinfunction "A_1") (pintype "passive"))
      (node (ref "R4") (pin "1") (pinfunction "1_1") (pintype "passive"))
      (node (ref "sh1.0-6p") (pin "1") (pinfunction "1_1") (pintype "passive"))
      (node (ref "sh1.0-6p") (pin "2") (pinfunction "2_2") (pintype "passive"))
      (node (ref "sh1.0-6p") (pin "3") (pinfunction "3_3") (pintype "passive"))
    )
    (net (code "113") (name "VCC_3.3V") (class "Default")
      (node (ref "C5") (pin "2") (pinfunction "2_2") (pintype "passive"))
      (node (ref "R20") (pin "2") (pinfunction "2_2") (pintype "passive"))
      (node (ref "R7") (pin "1") (pinfunction "1_1") (pintype "passive"))
      (node (ref "T4") (pin "1") (pinfunction "1_1") (pintype "passive"))
      (node (ref "U10") (pin "4") (pinfunction "4_4") (pintype "passive"))
      (node (ref "U11") (pin "5") (pinfunction "OUT_5") (pintype "passive"))
      (node (ref "U15") (pin "100") (pinfunction "VDD_3_100") (pintype "passive"))
      (node (ref "U15") (pin "11") (pinfunction "VDD_5_11") (pintype "passive"))
      (node (ref "U15") (pin "19") (pinfunction "VDD_19") (pintype "passive"))
      (node (ref "U15") (pin "21") (pinfunction "VREF+_21") (pintype "passive"))
      (node (ref "U15") (pin "22") (pinfunction "VDDA_22") (pintype "passive"))
      (node (ref "U15") (pin "28") (pinfunction "VDD_4_28") (pintype "passive"))
      (node (ref "U15") (pin "50") (pinfunction "VDD_1_50") (pintype "passive"))
      (node (ref "U15") (pin "6") (pinfunction "VBAT_6") (pintype "passive"))
      (node (ref "U15") (pin "75") (pinfunction "VDD_2_75") (pintype "passive"))
      (node (ref "W1") (pin "3") (pinfunction "/WP_3") (pintype "passive"))
      (node (ref "W1") (pin "7") (pinfunction "/HOLD_7") (pintype "passive"))
      (node (ref "W1") (pin "8") (pinfunction "VCC_8") (pintype "passive"))
    )
    (net (code "114") (name "VCC_5.0V") (class "Default")
      (node (ref "C3") (pin "2") (pinfunction "2_2") (pintype "passive"))
      (node (ref "C4") (pin "2") (pinfunction "2_2") (pintype "passive"))
      (node (ref "D1") (pin "2") (pinfunction "K_2") (pintype "passive"))
      (node (ref "H2") (pin "1") (pinfunction "1_1") (pintype "passive"))
      (node (ref "H2") (pin "2") (pinfunction "2_2") (pintype "passive"))
      (node (ref "H2") (pin "3") (pinfunction "3_3") (pintype "passive"))
      (node (ref "H2") (pin "4") (pinfunction "4_4") (pintype "passive"))
      (node (ref "H4") (pin "8") (pinfunction "8_8") (pintype "passive"))
      (node (ref "LX_IMU") (pin "2") (pinfunction "5V_2") (pintype "passive"))
      (node (ref "P1") (pin "2") (pinfunction "2_2") (pintype "passive"))
      (node (ref "P2_IMU") (pin "2") (pinfunction "5V_2") (pintype "passive"))
      (node (ref "R31") (pin "1") (pinfunction "1_1") (pintype "passive"))
      (node (ref "RGB") (pin "1") (pinfunction "VCC_1") (pintype "passive"))
      (node (ref "U11") (pin "1") (pinfunction "EN_1") (pintype "passive"))
      (node (ref "U11") (pin "3") (pinfunction "IN_3") (pintype "passive"))
      (node (ref "U16") (pin "1") (pinfunction "1_1") (pintype "passive"))
      (node (ref "U2") (pin "1") (pinfunction "VDD_1") (pintype "passive"))
      (node (ref "U3") (pin "1") (pinfunction "1_1") (pintype "passive"))
      (node (ref "U4") (pin "1") (pinfunction "1_1") (pintype "passive"))
      (node (ref "U5") (pin "1") (pinfunction "1_1") (pintype "passive"))
      (node (ref "U6") (pin "1") (pinfunction "1_1") (pintype "passive"))
      (node (ref "U7") (pin "1") (pinfunction "1_1") (pintype "passive"))
      (node (ref "U8") (pin "2") (pinfunction "2_2") (pintype "passive"))
      (node (ref "U9") (pin "2") (pinfunction "2_2") (pintype "passive"))
    )
    (net (code "115") (name "VCC_IN") (class "Default")
      (node (ref "D2") (pin "2") (pinfunction "K_2") (pintype "passive"))
      (node (ref "T1") (pin "1") (pinfunction "1_1") (pintype "passive"))
      (node (ref "U1") (pin "7") (pinfunction "VIN_7") (pintype "passive"))
    )
    (net (code "116") (name "unconnected-(U1-ENA-Pad5)") (class "Default")
      (node (ref "U1") (pin "5") (pinfunction "ENA_5") (pintype "passive"))
    )
    (net (code "117") (name "unconnected-(U1-NC-Pad2)") (class "Default")
      (node (ref "U1") (pin "2") (pinfunction "NC_2") (pintype "passive"))
    )
    (net (code "118") (name "unconnected-(U1-NC-Pad3)") (class "Default")
      (node (ref "U1") (pin "3") (pinfunction "NC_3") (pintype "passive"))
    )
    (net (code "119") (name "unconnected-(U2-NCC-Pad4)") (class "Default")
      (node (ref "U2") (pin "4") (pinfunction "NCC_4") (pintype "passive"))
    )
    (net (code "120") (name "unconnected-(U15-ETH_MDC{slash}ADC123_IN11{slash}PC1-Pad16)") (class "Default")
      (node (ref "U15") (pin "16") (pinfunction "ETH_MDC/ADC123_IN11/PC1_16") (pintype "passive"))
    )
    (net (code "121") (name "unconnected-(U15-ETH_RXD0{slash}ADC12_IN14{slash}PC4-Pad33)") (class "Default")
      (node (ref "U15") (pin "33") (pinfunction "ETH_RXD0/ADC12_IN14/PC4_33") (pintype "passive"))
    )
    (net (code "122") (name "unconnected-(U15-FSMC_A16{slash}USART3_CTS{slash}PD11-Pad58)") (class "Default")
      (node (ref "U15") (pin "58") (pinfunction "FSMC_A16/USART3_CTS/PD11_58") (pintype "passive"))
    )
    (net (code "123") (name "unconnected-(U15-FSMC_CLK{slash}USART2_CTS{slash}PD3-Pad84)") (class "Default")
      (node (ref "U15") (pin "84") (pinfunction "FSMC_CLK/USART2_CTS/PD3_84") (pintype "passive"))
    )
    (net (code "124") (name "unconnected-(U15-FSMC_D3{slash}CAN1_TX{slash}PD1-Pad82)") (class "Default")
      (node (ref "U15") (pin "82") (pinfunction "FSMC_D3/CAN1_TX/PD1_82") (pintype "passive"))
    )
    (net (code "125") (name "unconnected-(U15-FSMC_D4{slash}PE7-Pad38)") (class "Default")
      (node (ref "U15") (pin "38") (pinfunction "FSMC_D4/PE7_38") (pintype "passive"))
    )
    (net (code "126") (name "unconnected-(U15-FSMC_D5{slash}PE8-Pad39)") (class "Default")
      (node (ref "U15") (pin "39") (pinfunction "FSMC_D5/PE8_39") (pintype "passive"))
    )
    (net (code "127") (name "unconnected-(U15-FSMC_D7{slash}PE10-Pad41)") (class "Default")
      (node (ref "U15") (pin "41") (pinfunction "FSMC_D7/PE10_41") (pintype "passive"))
    )
    (net (code "128") (name "unconnected-(U15-FSMC_D9{slash}PE12-Pad43)") (class "Default")
      (node (ref "U15") (pin "43") (pinfunction "FSMC_D9/PE12_43") (pintype "passive"))
    )
    (net (code "129") (name "unconnected-(U15-FSMC_D12{slash}PE15-Pad46)") (class "Default")
      (node (ref "U15") (pin "46") (pinfunction "FSMC_D12/PE15_46") (pintype "passive"))
    )
    (net (code "130") (name "unconnected-(U15-FSMC_D13{slash}USART3_TX{slash}PD8-Pad55)") (class "Default")
      (node (ref "U15") (pin "55") (pinfunction "FSMC_D13/USART3_TX/PD8_55") (pintype "passive"))
    )
    (net (code "131") (name "unconnected-(U15-FSMC_D14{slash}USART3_RX{slash}PD9-Pad56)") (class "Default")
      (node (ref "U15") (pin "56") (pinfunction "FSMC_D14/USART3_RX/PD9_56") (pintype "passive"))
    )
    (net (code "132") (name "unconnected-(U15-FSMC_D15{slash}USART3_CK{slash}PD10_P_P-Pad57)") (class "Default")
      (node (ref "U15") (pin "57") (pinfunction "FSMC_D15/USART3_CK/PD10_P_P_57") (pintype "passive"))
    )
    (net (code "133") (name "unconnected-(U15-FSMC_NOE{slash}USART2_RTS{slash}PD4-Pad85)") (class "Default")
      (node (ref "U15") (pin "85") (pinfunction "FSMC_NOE/USART2_RTS/PD4_85") (pintype "passive"))
    )
    (net (code "134") (name "unconnected-(U15-I2S_CKIN{slash}MCO2{slash}SDIO_D1{slash}I2C3_SDA{slash}DCMI_D3{slash}PC9-Pad66)") (class "Default")
      (node (ref "U15") (pin "66") (pinfunction "I2S_CKIN/MCO2/SDIO_D1/I2C3_SDA/DCMI_D3/PC9_66") (pintype "passive"))
    )
    (net (code "135") (name "unconnected-(U15-OTG_HS_ULPI_STP{slash}EVENTOUT{slash}PC0-Pad15)") (class "Default")
      (node (ref "U15") (pin "15") (pinfunction "OTG_HS_ULPI_STP/EVENTOUT/PC0_15") (pintype "passive"))
    )
    (net (code "136") (name "unconnected-(U15-PA2{slash}USART2_TX{slash}ADC123_IN2{slash}ETH_MDIO-Pad25)") (class "Default")
      (node (ref "U15") (pin "25") (pinfunction "PA2/USART2_TX/ADC123_IN2/ETH_MDIO_25") (pintype "passive"))
    )
    (net (code "137") (name "unconnected-(U15-PA3{slash}USART2_RX{slash}OTG_HS_ULPI_D0{slash}ADC123_IN3-Pad26)") (class "Default")
      (node (ref "U15") (pin "26") (pinfunction "PA3/USART2_RX/OTG_HS_ULPI_D0/ADC123_IN3_26") (pintype "passive"))
    )
    (net (code "138") (name "unconnected-(U15-PA8{slash}MCO1{slash}I2C3_SCL{slash}OTG_FS_SOF-Pad67)") (class "Default")
      (node (ref "U15") (pin "67") (pinfunction "PA8/MCO1/I2C3_SCL/OTG_FS_SOF_67") (pintype "passive"))
    )
    (net (code "139") (name "unconnected-(U15-PA15{slash}JTDI{slash}I2S3_WS-Pad77)") (class "Default")
      (node (ref "U15") (pin "77") (pinfunction "PA15/JTDI/I2S3_WS_77") (pintype "passive"))
    )
    (net (code "140") (name "unconnected-(U15-PB3{slash}JTDO{slash}SPI3_SCK{slash}I2S3_CK{slash}SPI1_SCK-Pad89)") (class "Default")
      (node (ref "U15") (pin "89") (pinfunction "PB3/JTDO/SPI3_SCK/I2S3_CK/SPI1_SCK_89") (pintype "passive"))
    )
    (net (code "141") (name "unconnected-(U15-PB4{slash}JNTRST{slash}SPI3_MISO{slash}SPI1_MISO{slash}I2S3ext_SD-Pad90)") (class "Default")
      (node (ref "U15") (pin "90") (pinfunction "PB4/JNTRST/SPI3_MISO/SPI1_MISO/I2S3ext_SD_90") (pintype "passive"))
    )
    (net (code "142") (name "unconnected-(U15-PB5{slash}CAN2_RX{slash}OTG_HS_ULPI_D7{slash}DCMI_D10{slash}I2S3_SD-Pad91)") (class "Default")
      (node (ref "U15") (pin "91") (pinfunction "PB5/CAN2_RX/OTG_HS_ULPI_D7/DCMI_D10/I2S3_SD_91") (pintype "passive"))
    )
    (net (code "143") (name "unconnected-(U15-PB6{slash}I2C1_SCL{slash}CAN2_TX{slash}OTG_FS_INTN{slash}DCMI_D5{slash}USART1_TX_2_2-Pad92)") (class "Default")
      (node (ref "U15") (pin "92") (pinfunction "PB6/I2C1_SCL/CAN2_TX/OTG_FS_INTN/DCMI_D5/USART1_TX_2_2_92") (pintype "passive"))
    )
    (net (code "144") (name "unconnected-(U15-PB7{slash}I2C1_SDA{slash}FSMC_NL{slash}DCMI_VSYNC{slash}USART1_RX-Pad93)") (class "Default")
      (node (ref "U15") (pin "93") (pinfunction "PB7/I2C1_SDA/FSMC_NL/DCMI_VSYNC/USART1_RX_93") (pintype "passive"))
    )
    (net (code "145") (name "unconnected-(U15-PB9{slash}I2S2_WS{slash}OTG_FS_SDA{slash}SDIO_D5{slash}DCMI_D7{slash}I2C1_SDA{slash}CAN1_TX-Pad96)") (class "Default")
      (node (ref "U15") (pin "96") (pinfunction "PB9/I2S2_WS/OTG_FS_SDA/SDIO_D5/DCMI_D7/I2C1_SDA/CAN1_TX_96") (pintype "passive"))
    )
    (net (code "146") (name "unconnected-(U15-PC14-OSC32_IN-Pad8)") (class "Default")
      (node (ref "U15") (pin "8") (pinfunction "PC14-OSC32_IN_8") (pintype "passive"))
    )
    (net (code "147") (name "unconnected-(U15-PC15-OSC32_OUT-Pad9)") (class "Default")
      (node (ref "U15") (pin "9") (pinfunction "PC15-OSC32_OUT_9") (pintype "passive"))
    )
    (net (code "148") (name "unconnected-(U15-SDIO_D0{slash}DCMI_D2{slash}PC8-Pad65)") (class "Default")
      (node (ref "U15") (pin "65") (pinfunction "SDIO_D0/DCMI_D2/PC8_65") (pintype "passive"))
    )
    (net (code "149") (name "unconnected-(U15-SPI2_MISO{slash}OTG_HS_ULPI_DIR{slash}I2S2ext_SD{slash}ADC123_IN12{slash}PC2-Pad17)") (class "Default")
      (node (ref "U15") (pin "17") (pinfunction "SPI2_MISO/OTG_HS_ULPI_DIR/I2S2ext_SD/ADC123_IN12/PC2_17") (pintype "passive"))
    )
    (net (code "150") (name "unconnected-(U15-SPI2_MOSI{slash}I2S2_SD{slash}OTG_HS_ULPI_NXT{slash}ADC123_IN13{slash}PC3-Pad18)") (class "Default")
      (node (ref "U15") (pin "18") (pinfunction "SPI2_MOSI/I2S2_SD/OTG_HS_ULPI_NXT/ADC123_IN13/PC3_18") (pintype "passive"))
    )
    (net (code "151") (name "unconnected-(U15-TAMPER-RTC_AF1{slash}PC13-Pad7)") (class "Default")
      (node (ref "U15") (pin "7") (pinfunction "TAMPER-RTC_AF1/PC13_7") (pintype "passive"))
    )
    (net (code "152") (name "unconnected-(U15-TRACED0{slash}FSMC_A19{slash}PE3-Pad2)") (class "Default")
      (node (ref "U15") (pin "2") (pinfunction "TRACED0/FSMC_A19/PE3_2") (pintype "passive"))
    )
    (net (code "153") (name "unconnected-(U15-TRACED1{slash}FSMC_A20{slash}DCMI_D4{slash}PE4-Pad3)") (class "Default")
      (node (ref "U15") (pin "3") (pinfunction "TRACED1/FSMC_A20/DCMI_D4/PE4_3") (pintype "passive"))
    )
    (net (code "154") (name "unconnected-(U15-TRACED2{slash}FSMC_A21{slash}DCMI_D6{slash}PE5-Pad4)") (class "Default")
      (node (ref "U15") (pin "4") (pinfunction "TRACED2/FSMC_A21/DCMI_D6/PE5_4") (pintype "passive"))
    )
    (net (code "155") (name "unconnected-(U15-TRACED3{slash}FSMC_A22{slash}DCMI_D7{slash}PE6-Pad5)") (class "Default")
      (node (ref "U15") (pin "5") (pinfunction "TRACED3/FSMC_A22/DCMI_D7/PE6_5") (pintype "passive"))
    )
  )
)
